# Simetrica.net
KiCad netlist of a schematic drawn in Altium Designer
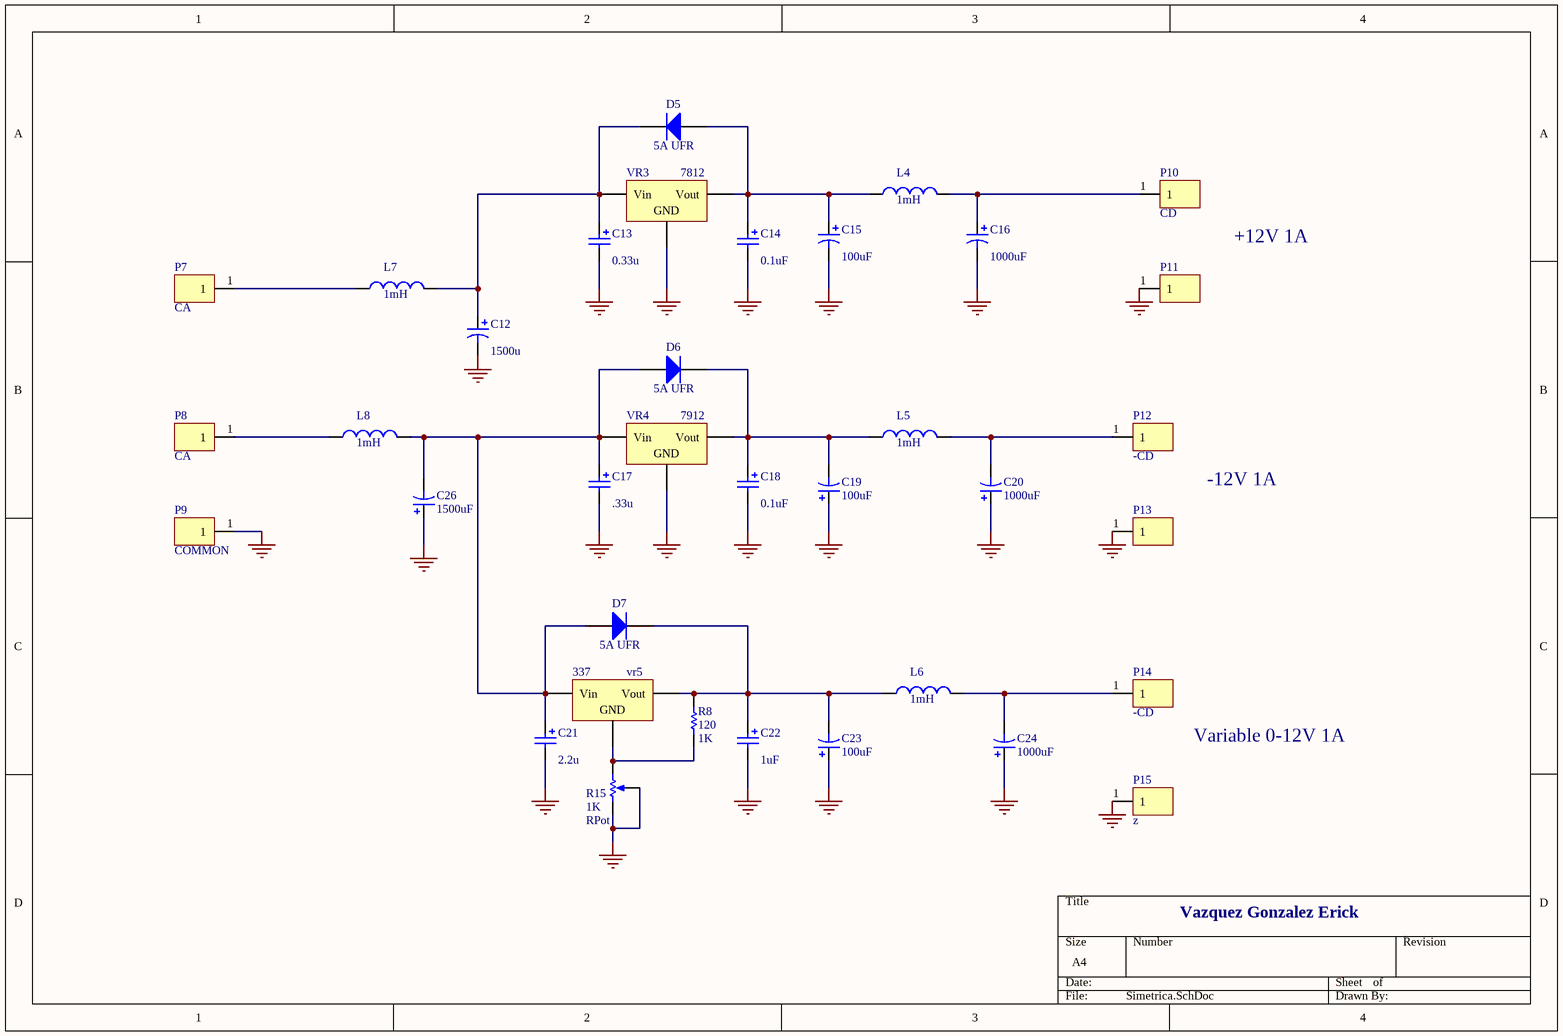
[diagram p0: Simetrica.SchDoc]

(export (version "E")
  (design (tool "Eeschema 10.0.6"))
  (components
    (comp (ref "337")
      (value "vr5")
      (footprint "TO-220-AB")
      (description "Voltage Regulator")
      (fields (field (name "PUBLISHER") "Altium Limited"))
      (libsource (lib "Miscellaneous Devices") (part "Volt Reg"))
    )
    (comp (ref "C12")
      (value "1500u")
      (footprint "CAP4700")
      (description "Polarized Capacitor (Radial)")
      (fields (field (name "Comment") "Cap Pol1") (field (name "PUBLISHER") "Altium Limited"))
      (libsource (lib "Miscellaneous Devices") (part "Cap Pol1"))
    )
    (comp (ref "C13")
      (value "0.33u")
      (footprint "RAD-0.1")
      (description "Polarized Capacitor (Axial)")
      (fields (field (name "Comment") "Cap Tan") (field (name "PUBLISHER") "Altium Limited"))
      (libsource (lib "Miscellaneous Devices") (part "Cap Pol2"))
    )
    (comp (ref "C14")
      (value "0.1uF")
      (footprint "RAD-0.1")
      (description "Polarized Capacitor (Axial)")
      (fields (field (name "Comment") "Cap Tan") (field (name "PUBLISHER") "Altium Limited"))
      (libsource (lib "Miscellaneous Devices") (part "Cap Pol2"))
    )
    (comp (ref "C15")
      (value "100uF")
      (footprint "RAD-0.1")
      (description "Polarized Capacitor (Radial)")
      (fields (field (name "Comment") "Cap Pol2") (field (name "PUBLISHER") "Altium Limited"))
      (libsource (lib "Miscellaneous Devices") (part "Cap Pol1"))
    )
    (comp (ref "C16")
      (value "1000uF")
      (footprint "CAP4700")
      (description "Polarized Capacitor (Radial)")
      (fields (field (name "Comment") "Cap Pol1") (field (name "PUBLISHER") "Altium Limited"))
      (libsource (lib "Miscellaneous Devices") (part "Cap Pol1"))
    )
    (comp (ref "C17")
      (value ".33u")
      (footprint "RAD-0.1")
      (description "Polarized Capacitor (Axial)")
      (fields (field (name "Comment") "Cap Tan") (field (name "PUBLISHER") "Altium Limited"))
      (libsource (lib "Miscellaneous Devices") (part "Cap Pol2"))
    )
    (comp (ref "C18")
      (value "0.1uF")
      (footprint "RAD-0.1")
      (description "Polarized Capacitor (Axial)")
      (fields (field (name "Comment") "Cap Tan") (field (name "PUBLISHER") "Altium Limited"))
      (libsource (lib "Miscellaneous Devices") (part "Cap Pol2"))
    )
    (comp (ref "C19")
      (value "100uF")
      (footprint "RAD-0.1")
      (description "Polarized Capacitor (Radial)")
      (fields (field (name "Comment") "Cap Pol2") (field (name "PUBLISHER") "Altium Limited"))
      (libsource (lib "Miscellaneous Devices") (part "Cap Pol1"))
    )
    (comp (ref "C20")
      (value "1000uF")
      (footprint "CAP4700")
      (description "Polarized Capacitor (Radial)")
      (fields (field (name "Comment") "Cap Pol1") (field (name "PUBLISHER") "Altium Limited"))
      (libsource (lib "Miscellaneous Devices") (part "Cap Pol1"))
    )
    (comp (ref "C21")
      (value "2.2u")
      (footprint "RAD-0.1")
      (description "Polarized Capacitor (Axial)")
      (fields (field (name "Comment") "Cap Tan") (field (name "PUBLISHER") "Altium Limited"))
      (libsource (lib "Miscellaneous Devices") (part "Cap Pol2"))
    )
    (comp (ref "C22")
      (value "1uF")
      (footprint "RAD-0.1")
      (description "Polarized Capacitor (Axial)")
      (fields (field (name "Comment") "Cap Tan") (field (name "PUBLISHER") "Altium Limited"))
      (libsource (lib "Miscellaneous Devices") (part "Cap Pol2"))
    )
    (comp (ref "C23")
      (value "100uF")
      (footprint "RAD-0.1")
      (description "Polarized Capacitor (Radial)")
      (fields (field (name "Comment") "Cap Pol2") (field (name "PUBLISHER") "Altium Limited"))
      (libsource (lib "Miscellaneous Devices") (part "Cap Pol1"))
    )
    (comp (ref "C24")
      (value "1000uF")
      (footprint "CAP4700")
      (description "Polarized Capacitor (Radial)")
      (fields (field (name "Comment") "Cap Pol1") (field (name "PUBLISHER") "Altium Limited"))
      (libsource (lib "Miscellaneous Devices") (part "Cap Pol1"))
    )
    (comp (ref "C26")
      (value "1500uF")
      (footprint "CAP4700")
      (description "Polarized Capacitor (Radial)")
      (fields (field (name "Comment") "Cap Pol1") (field (name "PUBLISHER") "Altium Limited"))
      (libsource (lib "Miscellaneous Devices") (part "Cap Pol1"))
    )
    (comp (ref "D5")
      (value "5A UFR")
      (footprint "DO-204AL")
      (description "3 Amp Medium Power Silicon Rectifier Diode")
      (fields (field (name "PUBLISHER") "Altium Limited"))
      (libsource (lib "Miscellaneous Devices") (part "Diode 1N5408"))
    )
    (comp (ref "D6")
      (value "5A UFR")
      (footprint "DO-204AL")
      (description "3 Amp Medium Power Silicon Rectifier Diode")
      (fields (field (name "PUBLISHER") "Altium Limited"))
      (libsource (lib "Miscellaneous Devices") (part "Diode 1N5408"))
    )
    (comp (ref "D7")
      (value "5A UFR")
      (footprint "DO-204AL")
      (description "3 Amp Medium Power Silicon Rectifier Diode")
      (fields (field (name "PUBLISHER") "Altium Limited"))
      (libsource (lib "Miscellaneous Devices") (part "Diode 1N5408"))
    )
    (comp (ref "L4")
      (value "1mH")
      (footprint "bobinita")
      (description "Inductor")
      (fields (field (name "Comment") "Inductor1") (field (name "PUBLISHER") "Altium Limited"))
      (libsource (lib "Miscellaneous Devices") (part "Inductor"))
    )
    (comp (ref "L5")
      (value "1mH")
      (footprint "bobinita")
      (description "Inductor")
      (fields (field (name "Comment") "Inductor1") (field (name "PUBLISHER") "Altium Limited"))
      (libsource (lib "Miscellaneous Devices") (part "Inductor"))
    )
    (comp (ref "L6")
      (value "1mH")
      (footprint "bobinita")
      (description "Inductor")
      (fields (field (name "Comment") "Inductor1") (field (name "PUBLISHER") "Altium Limited"))
      (libsource (lib "Miscellaneous Devices") (part "Inductor"))
    )
    (comp (ref "L7")
      (value "1mH")
      (footprint "bobinita")
      (description "Inductor")
      (fields (field (name "Comment") "Inductor1") (field (name "PUBLISHER") "Altium Limited"))
      (libsource (lib "Miscellaneous Devices") (part "Inductor"))
    )
    (comp (ref "L8")
      (value "1mH")
      (footprint "bobinita")
      (description "Inductor")
      (fields (field (name "Comment") "Inductor1") (field (name "PUBLISHER") "Altium Limited"))
      (libsource (lib "Miscellaneous Devices") (part "Inductor"))
    )
    (comp (ref "P7") (value "CA") (footprint "cONECTOR") (libsource (lib "") (part "Component_1_1")))
    (comp (ref "P8") (value "CA") (footprint "cONECTOR") (libsource (lib "") (part "Component_1_1")))
    (comp (ref "P9") (value "COMMON") (footprint "cONECTOR") (libsource (lib "") (part "Component_1_1")))
    (comp (ref "P10") (value "CD") (footprint "cONECTOR") (libsource (lib "Conector") (part "Component_1")))
    (comp (ref "P11") (value "~") (footprint "cONECTOR") (libsource (lib "Conector") (part "Component_1")))
    (comp (ref "P12") (value "-CD") (footprint "cONECTOR") (libsource (lib "Conector") (part "Component_1")))
    (comp (ref "P13") (value "X") (footprint "cONECTOR") (libsource (lib "Conector") (part "Component_1")))
    (comp (ref "P14") (value "-CD") (footprint "cONECTOR") (libsource (lib "Conector") (part "Component_1")))
    (comp (ref "P15") (value "z") (footprint "cONECTOR") (libsource (lib "Conector") (part "Component_1")))
    (comp (ref "R8")
      (value "120")
      (footprint "AXIAL-0.3")
      (description "Resistor")
      (fields (field (name "ALTIUM_VALUE") "1K") (field (name "PUBLISHER") "Altium Limited"))
      (libsource (lib "Miscellaneous Devices") (part "Res1"))
    )
    (comp (ref "R15")
      (value "RPot")
      (footprint "POT2")
      (description "Potentiometer")
      (fields (field (name "ALTIUM_VALUE") "1K") (field (name "PUBLISHER") "Altium Limited"))
      (libsource (lib "Miscellaneous Devices") (part "RPot"))
    )
    (comp (ref "VR3")
      (value "7812")
      (footprint "TO-220-AB")
      (description "Voltage Regulator")
      (fields (field (name "PUBLISHER") "Altium Limited"))
      (libsource (lib "Miscellaneous Devices") (part "Volt Reg"))
    )
    (comp (ref "VR4")
      (value "7912")
      (footprint "TO-220-AB")
      (description "Voltage Regulator")
      (fields (field (name "PUBLISHER") "Altium Limited"))
      (libsource (lib "Miscellaneous Devices") (part "Volt Reg"))
    )
  )
  (nets
    (net (code "1") (name "GND") (class "Default")
      (node (ref "C12") (pin "2") (pinfunction "2_2") (pintype "passive"))
      (node (ref "C13") (pin "2") (pinfunction "2_2") (pintype "passive"))
      (node (ref "C14") (pin "2") (pinfunction "2_2") (pintype "passive"))
      (node (ref "C15") (pin "2") (pinfunction "2_2") (pintype "passive"))
      (node (ref "C16") (pin "2") (pinfunction "2_2") (pintype "passive"))
      (node (ref "C17") (pin "2") (pinfunction "2_2") (pintype "passive"))
      (node (ref "C18") (pin "2") (pinfunction "2_2") (pintype "passive"))
      (node (ref "C19") (pin "1") (pinfunction "1_1") (pintype "passive"))
      (node (ref "C20") (pin "1") (pinfunction "1_1") (pintype "passive"))
      (node (ref "C21") (pin "2") (pinfunction "2_2") (pintype "passive"))
      (node (ref "C22") (pin "2") (pinfunction "2_2") (pintype "passive"))
      (node (ref "C23") (pin "1") (pinfunction "1_1") (pintype "passive"))
      (node (ref "C24") (pin "1") (pinfunction "1_1") (pintype "passive"))
      (node (ref "C26") (pin "1") (pinfunction "1_1") (pintype "passive"))
      (node (ref "P11") (pin "1") (pinfunction "1_1") (pintype "passive"))
      (node (ref "P13") (pin "1") (pinfunction "1_1") (pintype "passive"))
      (node (ref "P15") (pin "1") (pinfunction "1_1") (pintype "passive"))
      (node (ref "P9") (pin "1") (pinfunction "1_1") (pintype "passive"))
      (node (ref "R15") (pin "1") (pinfunction "TOP_1") (pintype "passive"))
      (node (ref "R15") (pin "3") (pinfunction "TAP_3") (pintype "passive"))
      (node (ref "VR3") (pin "2") (pinfunction "GND_2") (pintype "passive"))
      (node (ref "VR4") (pin "2") (pinfunction "GND_2") (pintype "passive"))
    )
    (net (code "2") (name "Net-(337-GND)") (class "Default")
      (node (ref "337") (pin "2") (pinfunction "GND_2") (pintype "passive"))
      (node (ref "R15") (pin "2") (pinfunction "BOT_2") (pintype "passive"))
      (node (ref "R8") (pin "1") (pinfunction "1_1") (pintype "passive"))
    )
    (net (code "3") (name "Net-(337-Vin)") (class "Default")
      (node (ref "337") (pin "1") (pinfunction "Vin_1") (pintype "passive"))
      (node (ref "C17") (pin "1") (pinfunction "1_1") (pintype "passive"))
      (node (ref "C21") (pin "1") (pinfunction "1_1") (pintype "passive"))
      (node (ref "C26") (pin "2") (pinfunction "2_2") (pintype "passive"))
      (node (ref "D6") (pin "1") (pinfunction "A_1") (pintype "passive"))
      (node (ref "D7") (pin "1") (pinfunction "A_1") (pintype "passive"))
      (node (ref "L8") (pin "2") (pinfunction "2_2") (pintype "passive"))
      (node (ref "VR4") (pin "1") (pinfunction "Vin_1") (pintype "passive"))
    )
    (net (code "4") (name "Net-(337-Vout)") (class "Default")
      (node (ref "337") (pin "3") (pinfunction "Vout_3") (pintype "passive"))
      (node (ref "C22") (pin "1") (pinfunction "1_1") (pintype "passive"))
      (node (ref "C23") (pin "2") (pinfunction "2_2") (pintype "passive"))
      (node (ref "D7") (pin "2") (pinfunction "K_2") (pintype "passive"))
      (node (ref "L6") (pin "1") (pinfunction "1_1") (pintype "passive"))
      (node (ref "R8") (pin "2") (pinfunction "2_2") (pintype "passive"))
    )
    (net (code "5") (name "Net-(C16-Pad1)") (class "Default")
      (node (ref "C16") (pin "1") (pinfunction "1_1") (pintype "passive"))
      (node (ref "L4") (pin "2") (pinfunction "2_2") (pintype "passive"))
      (node (ref "P10") (pin "1") (pinfunction "1_1") (pintype "passive"))
    )
    (net (code "6") (name "Net-(C20-Pad2)") (class "Default")
      (node (ref "C20") (pin "2") (pinfunction "2_2") (pintype "passive"))
      (node (ref "L5") (pin "2") (pinfunction "2_2") (pintype "passive"))
      (node (ref "P12") (pin "1") (pinfunction "1_1") (pintype "passive"))
    )
    (net (code "7") (name "Net-(C24-Pad2)") (class "Default")
      (node (ref "C24") (pin "2") (pinfunction "2_2") (pintype "passive"))
      (node (ref "L6") (pin "2") (pinfunction "2_2") (pintype "passive"))
      (node (ref "P14") (pin "1") (pinfunction "1_1") (pintype "passive"))
    )
    (net (code "8") (name "Net-(D5-A)") (class "Default")
      (node (ref "C14") (pin "1") (pinfunction "1_1") (pintype "passive"))
      (node (ref "C15") (pin "1") (pinfunction "1_1") (pintype "passive"))
      (node (ref "D5") (pin "1") (pinfunction "A_1") (pintype "passive"))
      (node (ref "L4") (pin "1") (pinfunction "1_1") (pintype "passive"))
      (node (ref "VR3") (pin "3") (pinfunction "Vout_3") (pintype "passive"))
    )
    (net (code "9") (name "Net-(D5-K)") (class "Default")
      (node (ref "C12") (pin "1") (pinfunction "1_1") (pintype "passive"))
      (node (ref "C13") (pin "1") (pinfunction "1_1") (pintype "passive"))
      (node (ref "D5") (pin "2") (pinfunction "K_2") (pintype "passive"))
      (node (ref "L7") (pin "2") (pinfunction "2_2") (pintype "passive"))
      (node (ref "VR3") (pin "1") (pinfunction "Vin_1") (pintype "passive"))
    )
    (net (code "10") (name "Net-(D6-K)") (class "Default")
      (node (ref "C18") (pin "1") (pinfunction "1_1") (pintype "passive"))
      (node (ref "C19") (pin "2") (pinfunction "2_2") (pintype "passive"))
      (node (ref "D6") (pin "2") (pinfunction "K_2") (pintype "passive"))
      (node (ref "L5") (pin "1") (pinfunction "1_1") (pintype "passive"))
      (node (ref "VR4") (pin "3") (pinfunction "Vout_3") (pintype "passive"))
    )
    (net (code "11") (name "Net-(L7-Pad1)") (class "Default")
      (node (ref "L7") (pin "1") (pinfunction "1_1") (pintype "passive"))
      (node (ref "P7") (pin "1") (pinfunction "1_1") (pintype "passive"))
    )
    (net (code "12") (name "Net-(L8-Pad1)") (class "Default")
      (node (ref "L8") (pin "1") (pinfunction "1_1") (pintype "passive"))
      (node (ref "P8") (pin "1") (pinfunction "1_1") (pintype "passive"))
    )
  )
)
